# Navigation_Controll.net
KiCad netlist of a schematic drawn in Altium Designer
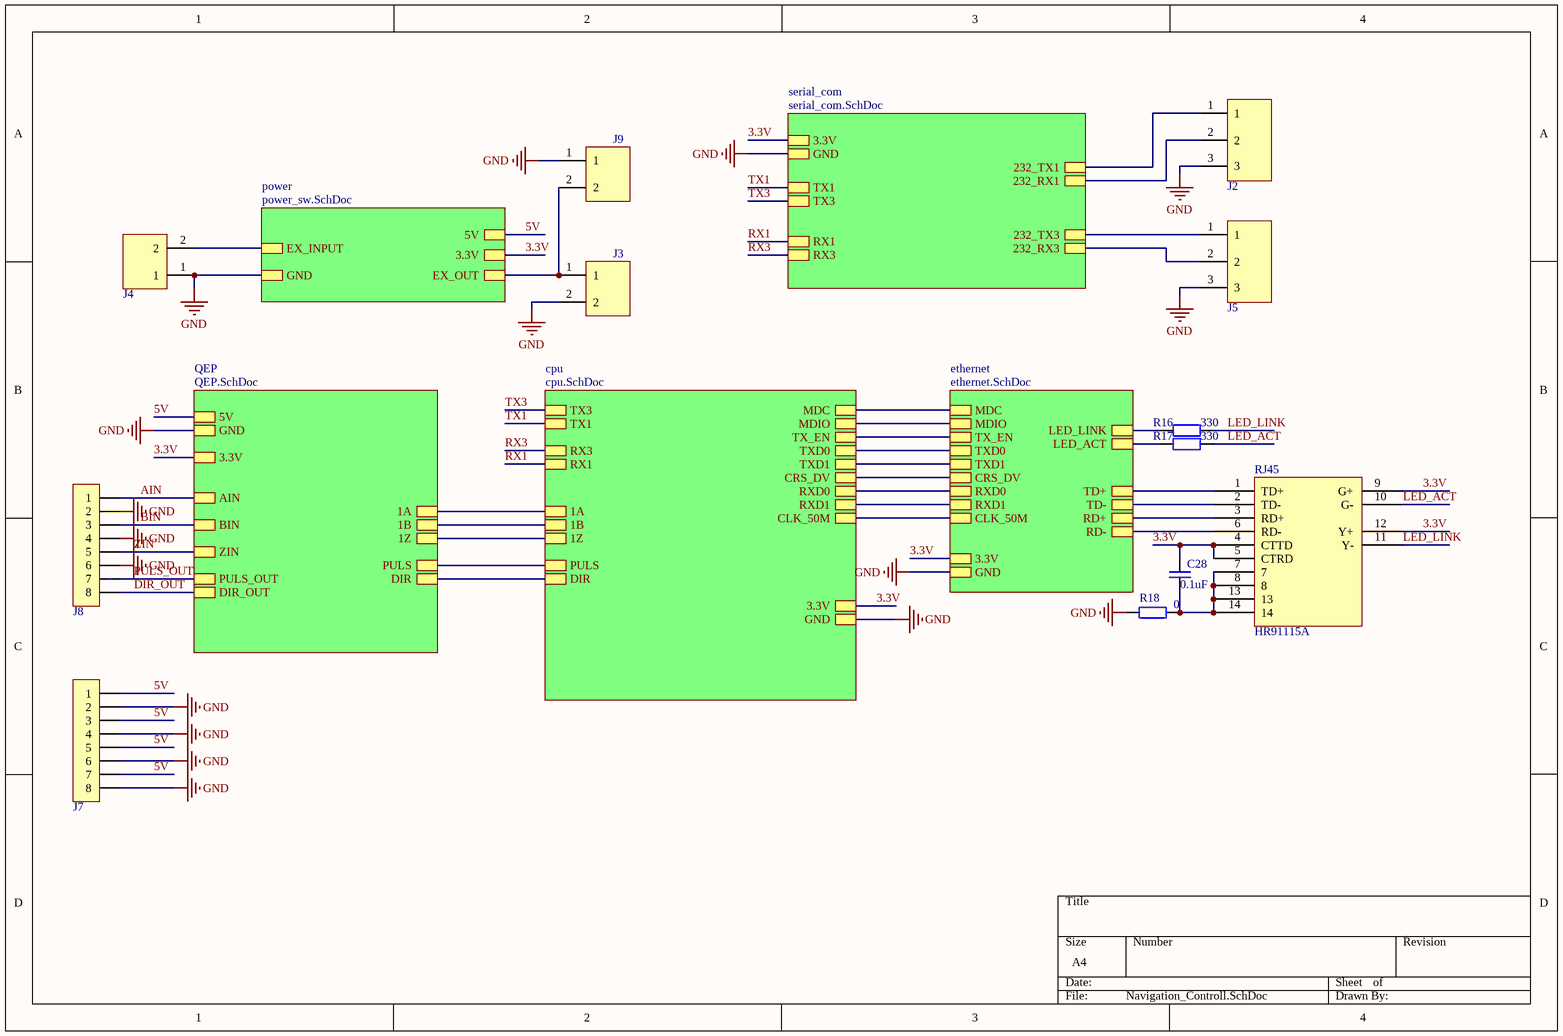
[diagram p0: Navigation_Controll.SchDoc]

(export (version "E")
  (design (tool "Eeschema 10.0.6"))
  (components
    (comp (ref "C28")
      (value "0.1uF")
      (footprint "CAP-0805")
      (fields (field (name "Comment") "CAP"))
      (libsource (lib "Schlib1") (part "CAP"))
    )
    (comp (ref "J2") (value "DG3P") (footprint "DG381-3P") (libsource (lib "Schlib1") (part "DG3P")))
    (comp (ref "J3") (value "DG2P") (footprint "DG381-2P") (libsource (lib "") (part "DG2P_1")))
    (comp (ref "J4") (value "DG2P") (footprint "DG508-2P") (libsource (lib "Schlib1") (part "DG2P")))
    (comp (ref "J5") (value "DG3P") (footprint "DG381-3P") (libsource (lib "Schlib1") (part "DG3P")))
    (comp (ref "J7") (value "HDR1*8") (footprint "KF128L-8P") (libsource (lib "Schlib1") (part "HDR1*8")))
    (comp (ref "J8") (value "HDR1*8") (footprint "KF128L-8P") (libsource (lib "Schlib1") (part "HDR1*8")))
    (comp (ref "J9") (value "DG2P") (footprint "DG381-2P") (libsource (lib "") (part "DG2P_1")))
    (comp (ref "R16")
      (value "330")
      (footprint "RES-0805")
      (fields (field (name "Comment") "RES"))
      (libsource (lib "Schlib1") (part "RES"))
    )
    (comp (ref "R17")
      (value "330")
      (footprint "RES-0805")
      (fields (field (name "Comment") "RES"))
      (libsource (lib "Schlib1") (part "RES"))
    )
    (comp (ref "R18")
      (value "0")
      (footprint "RES-0805")
      (fields (field (name "Comment") "RES"))
      (libsource (lib "Schlib1") (part "RES"))
    )
    (comp (ref "RJ45")
      (value "HR91115A")
      (footprint "RJ45_ISO")
      (libsource (lib "Schlib1") (part "NET_PORT"))
    )
  )
  (nets
    (net (code "4") (name "/3.3V") (class "Default")
      (node (ref "C28") (pin "2") (pintype "passive"))
      (node (ref "RJ45") (pin "12") (pinfunction "Y+_12") (pintype "passive"))
      (node (ref "RJ45") (pin "4") (pinfunction "CTTD_4") (pintype "passive"))
      (node (ref "RJ45") (pin "5") (pinfunction "CTRD_5") (pintype "passive"))
      (node (ref "RJ45") (pin "9") (pinfunction "G+_9") (pintype "passive"))
    )
    (net (code "5") (name "/5V") (class "Default")
      (node (ref "J7") (pin "1") (pinfunction "1_1") (pintype "passive"))
      (node (ref "J7") (pin "3") (pinfunction "3_3") (pintype "passive"))
      (node (ref "J7") (pin "5") (pinfunction "5_5") (pintype "passive"))
      (node (ref "J7") (pin "7") (pinfunction "7_7") (pintype "passive"))
    )
    (net (code "6") (name "/232_RX1") (class "Default")
      (node (ref "J2") (pin "2") (pinfunction "2_2") (pintype "passive"))
    )
    (net (code "7") (name "/232_RX3") (class "Default")
      (node (ref "J5") (pin "2") (pinfunction "2_2") (pintype "passive"))
    )
    (net (code "8") (name "/232_TX1") (class "Default")
      (node (ref "J2") (pin "1") (pinfunction "1_1") (pintype "passive"))
    )
    (net (code "9") (name "/232_TX3") (class "Default")
      (node (ref "J5") (pin "1") (pinfunction "1_1") (pintype "passive"))
    )
    (net (code "10") (name "/AIN") (class "Default")
      (node (ref "J8") (pin "1") (pinfunction "1_1") (pintype "passive"))
    )
    (net (code "11") (name "/BIN") (class "Default")
      (node (ref "J8") (pin "3") (pinfunction "3_3") (pintype "passive"))
    )
    (net (code "15") (name "/DIR_OUT") (class "Default")
      (node (ref "J8") (pin "8") (pinfunction "8_8") (pintype "passive"))
    )
    (net (code "16") (name "/EX_INPUT") (class "Default")
      (node (ref "J4") (pin "2") (pinfunction "2_2") (pintype "passive"))
    )
    (net (code "17") (name "/EX_OUT") (class "Default")
      (node (ref "J3") (pin "1") (pinfunction "1_1") (pintype "passive"))
      (node (ref "J9") (pin "2") (pinfunction "2_2") (pintype "passive"))
    )
    (net (code "18") (name "/LED_ACT") (class "Default")
      (node (ref "R17") (pin "2") (pintype "passive"))
      (node (ref "RJ45") (pin "10") (pinfunction "G-_10") (pintype "passive"))
    )
    (net (code "19") (name "/LED_ACT_1") (class "Default") (node (ref "R17") (pin "1") (pintype "passive")))
    (net (code "20") (name "/LED_LINK") (class "Default")
      (node (ref "R16") (pin "2") (pintype "passive"))
      (node (ref "RJ45") (pin "11") (pinfunction "Y-_11") (pintype "passive"))
    )
    (net (code "21") (name "/LED_LINK_1") (class "Default") (node (ref "R16") (pin "1") (pintype "passive")))
    (net (code "25") (name "/PULS_OUT") (class "Default")
      (node (ref "J8") (pin "7") (pinfunction "7_7") (pintype "passive"))
    )
    (net (code "26") (name "/RD+") (class "Default")
      (node (ref "RJ45") (pin "3") (pinfunction "RD+_3") (pintype "passive"))
    )
    (net (code "27") (name "/RD-") (class "Default")
      (node (ref "RJ45") (pin "6") (pinfunction "RD-_6") (pintype "passive"))
    )
    (net (code "32") (name "/TD+") (class "Default")
      (node (ref "RJ45") (pin "1") (pinfunction "TD+_1") (pintype "passive"))
    )
    (net (code "33") (name "/TD-") (class "Default")
      (node (ref "RJ45") (pin "2") (pinfunction "TD-_2") (pintype "passive"))
    )
    (net (code "39") (name "/ZIN") (class "Default")
      (node (ref "J8") (pin "5") (pinfunction "5_5") (pintype "passive"))
    )
    (net (code "40") (name "GND") (class "Default")
      (node (ref "J2") (pin "3") (pinfunction "3_3") (pintype "passive"))
      (node (ref "J3") (pin "2") (pinfunction "2_2") (pintype "passive"))
      (node (ref "J4") (pin "1") (pinfunction "1_1") (pintype "passive"))
      (node (ref "J5") (pin "3") (pinfunction "3_3") (pintype "passive"))
      (node (ref "J7") (pin "2") (pinfunction "2_2") (pintype "passive"))
      (node (ref "J7") (pin "4") (pinfunction "4_4") (pintype "passive"))
      (node (ref "J7") (pin "6") (pinfunction "6_6") (pintype "passive"))
      (node (ref "J7") (pin "8") (pinfunction "8_8") (pintype "passive"))
      (node (ref "J8") (pin "2") (pinfunction "2_2") (pintype "passive"))
      (node (ref "J8") (pin "4") (pinfunction "4_4") (pintype "passive"))
      (node (ref "J8") (pin "6") (pinfunction "6_6") (pintype "passive"))
      (node (ref "J9") (pin "1") (pinfunction "1_1") (pintype "passive"))
      (node (ref "R18") (pin "1") (pintype "passive"))
    )
    (net (code "41") (name "Net-(C28-Pad1)") (class "Default")
      (node (ref "C28") (pin "1") (pintype "passive"))
      (node (ref "R18") (pin "2") (pintype "passive"))
      (node (ref "RJ45") (pin "13") (pinfunction "13_13") (pintype "passive"))
      (node (ref "RJ45") (pin "14") (pinfunction "14_14") (pintype "passive"))
      (node (ref "RJ45") (pin "7") (pinfunction "7_7") (pintype "passive"))
      (node (ref "RJ45") (pin "8") (pinfunction "8_8") (pintype "passive"))
    )
  )
)
